# sensor_voltage.net
KiCad netlist of a schematic drawn in EAGLE
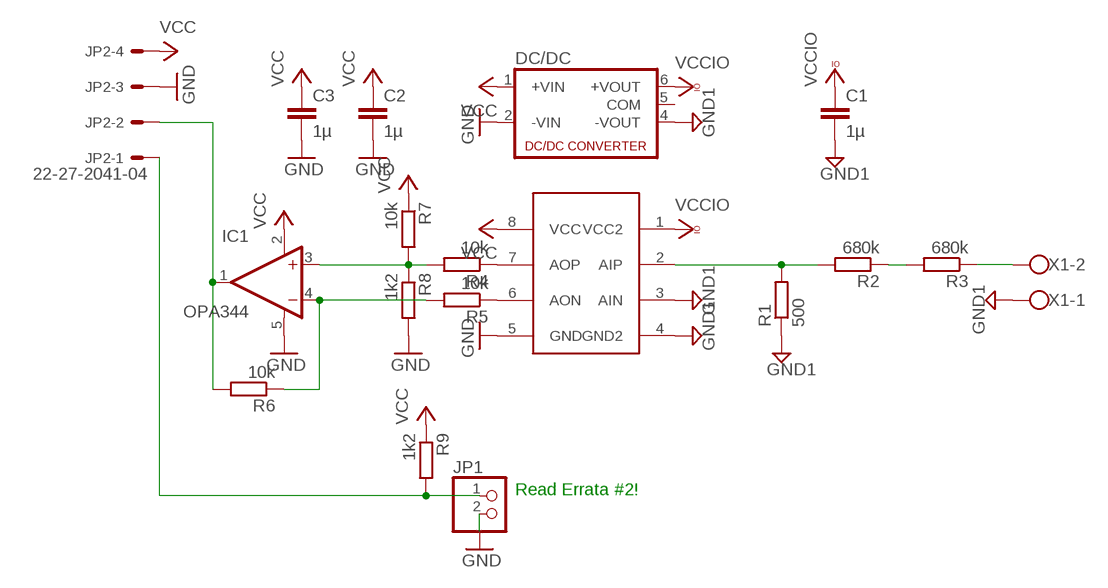
[diagram p0: schematic, sheet 1]

(export (version "E")
  (design (tool "Eeschema 10.0.6"))
  (components
    (comp (ref "C1")
      (value "1µ")
      (footprint "eagle-import:C025-024X044")
      (libsource (lib "eagle-import") (part "C-EU025-024X044"))
    )
    (comp (ref "C2")
      (value "1µ")
      (footprint "eagle-import:C025-024X044")
      (libsource (lib "eagle-import") (part "C-EU025-024X044"))
    )
    (comp (ref "C3")
      (value "1µ")
      (footprint "eagle-import:C025-024X044")
      (libsource (lib "eagle-import") (part "C-EU025-024X044"))
    )
    (comp (ref "DC/DC")
      (value "MEV3")
      (footprint "eagle-import:NMA")
      (libsource (lib "eagle-import") (part "MEV3"))
    )
    (comp (ref "IC1")
      (value "OPA344")
      (footprint "eagle-import:SOT23-5")
      (libsource (lib "eagle-import") (part "OPA344"))
    )
    (comp (ref "IC2")
      (value "SI8920")
      (footprint "eagle-import:DIP8")
      (libsource (lib "eagle-import") (part "SI8920"))
    )
    (comp (ref "JP1")
      (value "PINHD-1X2")
      (footprint "eagle-import:1X02")
      (libsource (lib "eagle-import") (part "PINHD-1X2"))
    )
    (comp (ref "JP2")
      (value "22-27-2041-04")
      (footprint "eagle-import:6410-04")
      (libsource (lib "eagle-import") (part "22-?-0427-2041"))
    )
    (comp (ref "R1")
      (value "500")
      (footprint "eagle-import:0207_10")
      (libsource (lib "eagle-import") (part "R-EU_0207/10"))
    )
    (comp (ref "R2")
      (value "680k")
      (footprint "eagle-import:0207_10")
      (libsource (lib "eagle-import") (part "R-EU_0207/10"))
    )
    (comp (ref "R3")
      (value "680k")
      (footprint "eagle-import:0207_10")
      (libsource (lib "eagle-import") (part "R-EU_0207/10"))
    )
    (comp (ref "R4")
      (value "10k")
      (footprint "eagle-import:0207_10")
      (libsource (lib "eagle-import") (part "R-EU_0207/10"))
    )
    (comp (ref "R5")
      (value "10k")
      (footprint "eagle-import:0207_10")
      (libsource (lib "eagle-import") (part "R-EU_0207/10"))
    )
    (comp (ref "R6")
      (value "10k")
      (footprint "eagle-import:0207_10")
      (libsource (lib "eagle-import") (part "R-EU_0207/10"))
    )
    (comp (ref "R7")
      (value "10k")
      (footprint "eagle-import:0207_10")
      (libsource (lib "eagle-import") (part "R-EU_0207/10"))
    )
    (comp (ref "R8")
      (value "1k2")
      (footprint "eagle-import:0207_10")
      (libsource (lib "eagle-import") (part "R-EU_0207/10"))
    )
    (comp (ref "R9")
      (value "1k2")
      (footprint "eagle-import:0207_10")
      (libsource (lib "eagle-import") (part "R-EU_0207/10"))
    )
    (comp (ref "X1")
      (value "W237-102")
      (footprint "eagle-import:W237-102")
      (fields (field (name "MPN") "237-102"))
      (libsource (lib "eagle-import") (part "W237-102"))
    )
  )
  (nets
    (net (code "1") (name "GND") (class "Default")
      (node (ref "C2") (pin "2") (pinfunction "2_2") (pintype "passive"))
      (node (ref "C3") (pin "2") (pinfunction "2_2") (pintype "passive"))
      (node (ref "DC/DC") (pin "2") (pinfunction "-VIN_2") (pintype "passive"))
      (node (ref "IC1") (pin "5") (pinfunction "V+_5") (pintype "power_in"))
      (node (ref "IC2") (pin "5") (pinfunction "GND_5") (pintype "bidirectional"))
      (node (ref "JP1") (pin "2") (pinfunction "2_2") (pintype "passive"))
      (node (ref "JP2") (pin "3") (pinfunction "S_3") (pintype "passive"))
      (node (ref "R8") (pin "2") (pinfunction "2_2") (pintype "passive"))
    )
    (net (code "2") (name "GND1") (class "Default")
      (node (ref "C1") (pin "2") (pinfunction "2_2") (pintype "passive"))
      (node (ref "DC/DC") (pin "4") (pinfunction "-VOUT_4") (pintype "passive"))
      (node (ref "IC2") (pin "3") (pinfunction "AIN_3") (pintype "bidirectional"))
      (node (ref "IC2") (pin "4") (pinfunction "GND2_4") (pintype "bidirectional"))
      (node (ref "R1") (pin "1") (pinfunction "1_1") (pintype "passive"))
      (node (ref "X1") (pin "1") (pinfunction "KL_1") (pintype "passive"))
    )
    (net (code "3") (name "Net-(IC1-+IN)") (class "Default")
      (node (ref "IC1") (pin "3") (pinfunction "+IN_3") (pintype "input"))
      (node (ref "R4") (pin "2") (pinfunction "2_2") (pintype "passive"))
      (node (ref "R7") (pin "2") (pinfunction "2_2") (pintype "passive"))
      (node (ref "R8") (pin "1") (pinfunction "1_1") (pintype "passive"))
    )
    (net (code "4") (name "Net-(IC1--IN)") (class "Default")
      (node (ref "IC1") (pin "4") (pinfunction "-IN_4") (pintype "input"))
      (node (ref "R5") (pin "2") (pinfunction "2_2") (pintype "passive"))
      (node (ref "R6") (pin "1") (pinfunction "1_1") (pintype "passive"))
    )
    (net (code "5") (name "Net-(IC1-OUT)") (class "Default")
      (node (ref "IC1") (pin "1") (pinfunction "OUT_1") (pintype "output"))
      (node (ref "JP2") (pin "2") (pinfunction "S_2") (pintype "passive"))
      (node (ref "R6") (pin "2") (pinfunction "2_2") (pintype "passive"))
    )
    (net (code "6") (name "Net-(IC2-AIP)") (class "Default")
      (node (ref "IC2") (pin "2") (pinfunction "AIP_2") (pintype "bidirectional"))
      (node (ref "R1") (pin "2") (pinfunction "2_2") (pintype "passive"))
      (node (ref "R2") (pin "2") (pinfunction "2_2") (pintype "passive"))
    )
    (net (code "7") (name "Net-(IC2-AON)") (class "Default")
      (node (ref "IC2") (pin "6") (pinfunction "AON_6") (pintype "bidirectional"))
      (node (ref "R5") (pin "1") (pinfunction "1_1") (pintype "passive"))
    )
    (net (code "8") (name "Net-(IC2-AOP)") (class "Default")
      (node (ref "IC2") (pin "7") (pinfunction "AOP_7") (pintype "bidirectional"))
      (node (ref "R4") (pin "1") (pinfunction "1_1") (pintype "passive"))
    )
    (net (code "9") (name "Net-(JP2A-S)") (class "Default")
      (node (ref "JP1") (pin "1") (pinfunction "1_1") (pintype "passive"))
      (node (ref "JP2") (pin "1") (pinfunction "S_1") (pintype "passive"))
      (node (ref "R9") (pin "2") (pinfunction "2_2") (pintype "passive"))
    )
    (net (code "10") (name "Net-(R2-Pad1)") (class "Default")
      (node (ref "R2") (pin "1") (pinfunction "1_1") (pintype "passive"))
      (node (ref "R3") (pin "2") (pinfunction "2_2") (pintype "passive"))
    )
    (net (code "11") (name "Net-(X1B-KL)") (class "Default")
      (node (ref "R3") (pin "1") (pinfunction "1_1") (pintype "passive"))
      (node (ref "X1") (pin "2") (pinfunction "KL_2") (pintype "passive"))
    )
    (net (code "12") (name "VCC") (class "Default")
      (node (ref "C2") (pin "1") (pinfunction "1_1") (pintype "passive"))
      (node (ref "C3") (pin "1") (pinfunction "1_1") (pintype "passive"))
      (node (ref "DC/DC") (pin "1") (pinfunction "+VIN_1") (pintype "passive"))
      (node (ref "IC1") (pin "2") (pinfunction "V-_2") (pintype "power_in"))
      (node (ref "IC2") (pin "8") (pinfunction "VCC_8") (pintype "bidirectional"))
      (node (ref "JP2") (pin "4") (pinfunction "S_4") (pintype "passive"))
      (node (ref "R7") (pin "1") (pinfunction "1_1") (pintype "passive"))
      (node (ref "R9") (pin "1") (pinfunction "1_1") (pintype "passive"))
    )
    (net (code "13") (name "VCCIO") (class "Default")
      (node (ref "C1") (pin "1") (pinfunction "1_1") (pintype "passive"))
      (node (ref "DC/DC") (pin "6") (pinfunction "+VOUT_6") (pintype "passive"))
      (node (ref "IC2") (pin "1") (pinfunction "VCC2_1") (pintype "bidirectional"))
    )
    (net (code "14") (name "unconnected-(DC/DC-COM-Pad5)") (class "Default")
      (node (ref "DC/DC") (pin "5") (pinfunction "COM_5") (pintype "passive"))
    )
  )
)
